# GMSL_DESERIALIZER.net
KiCad netlist of a schematic drawn in Altium Designer
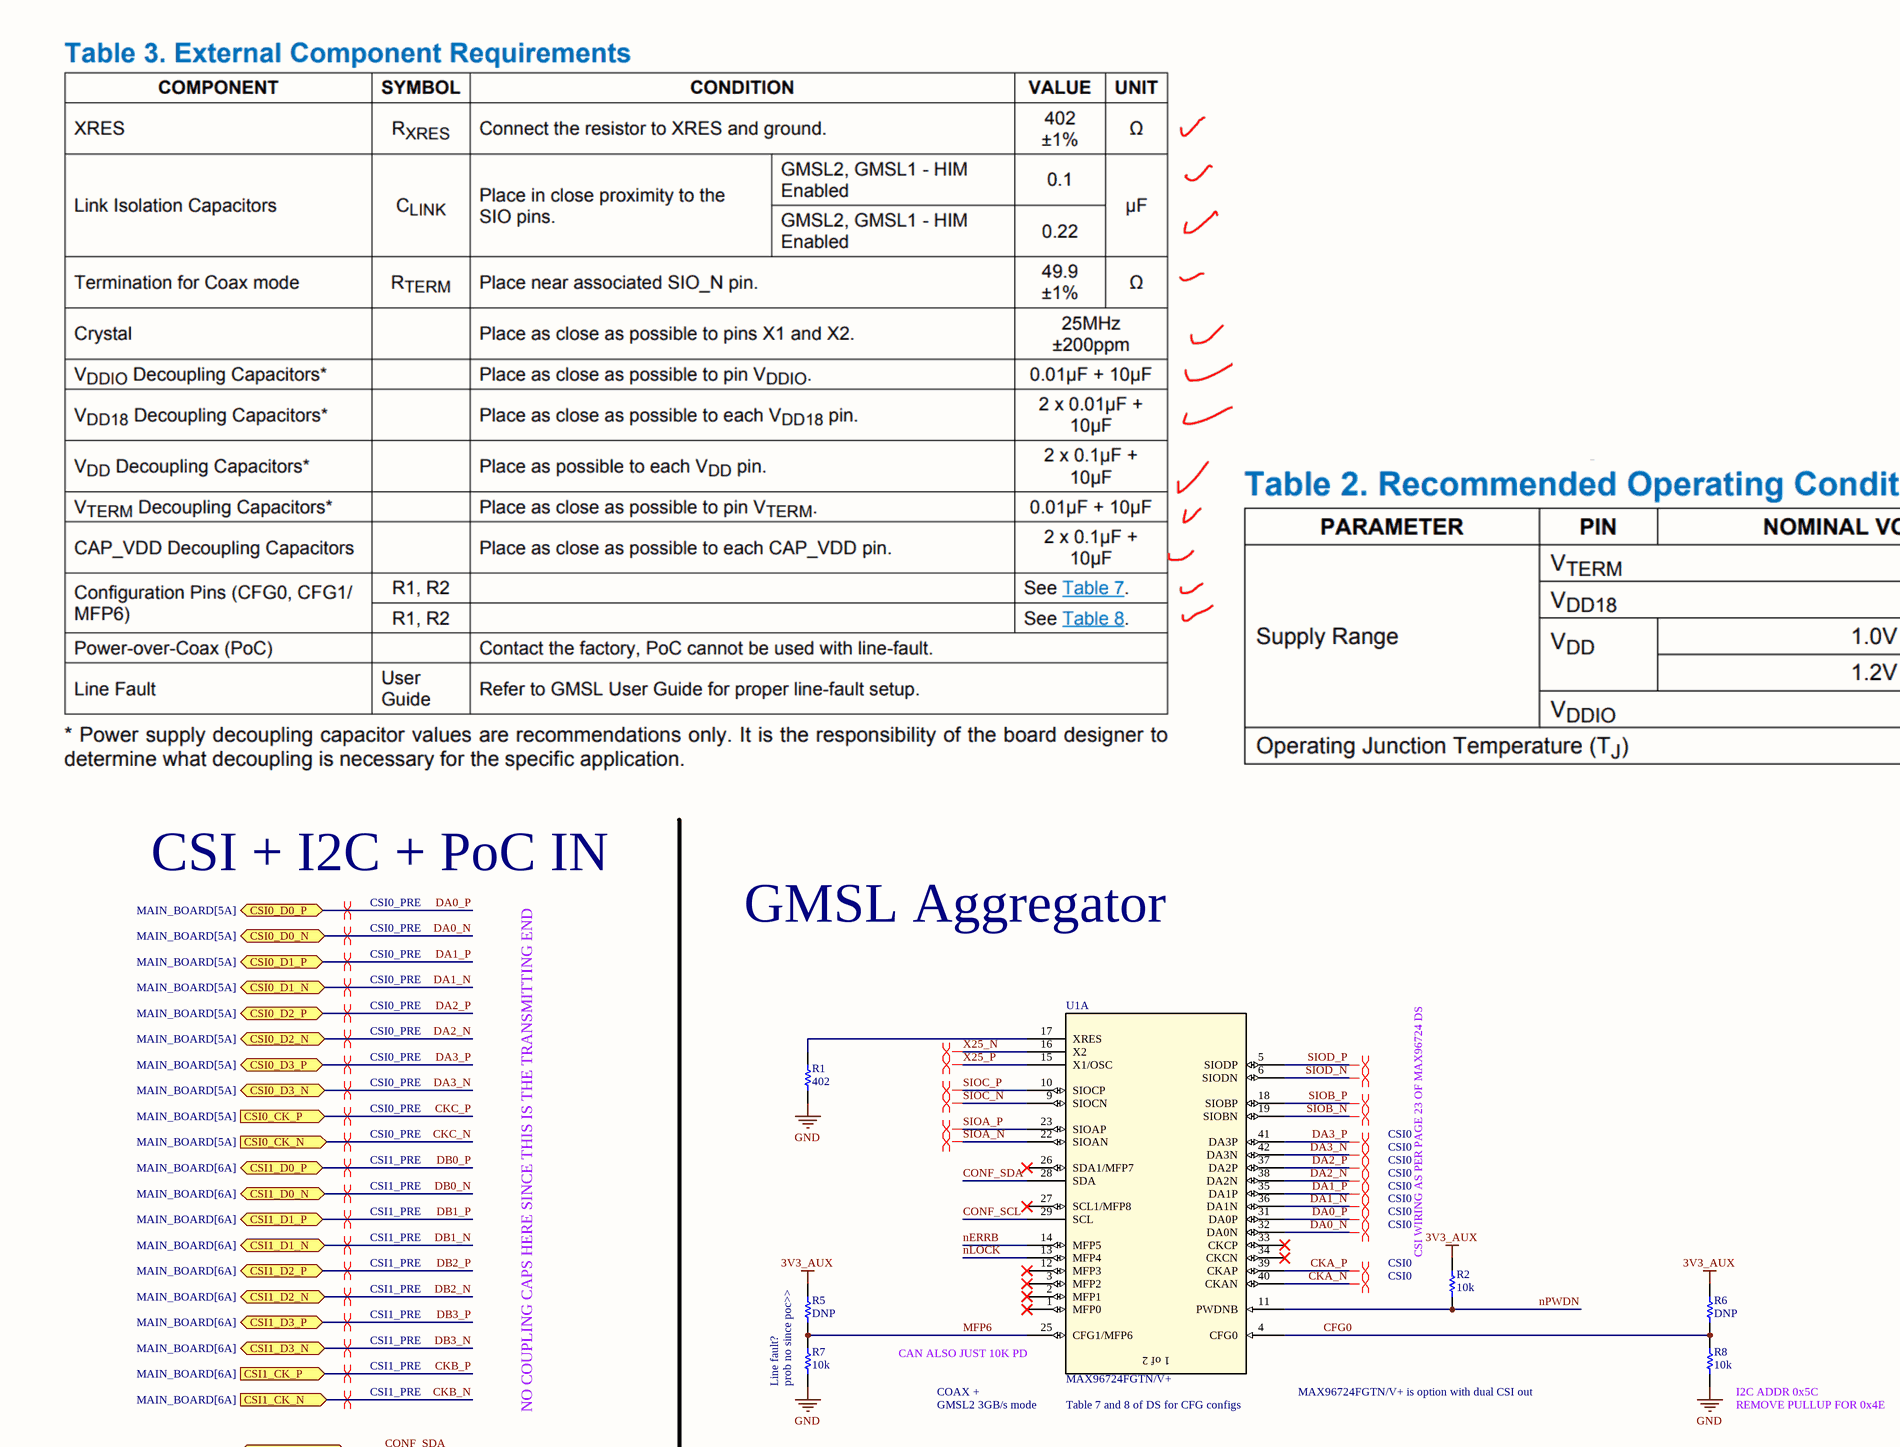
[diagram p0: GMSL_DESERIALIZER.SchDoc, top left]
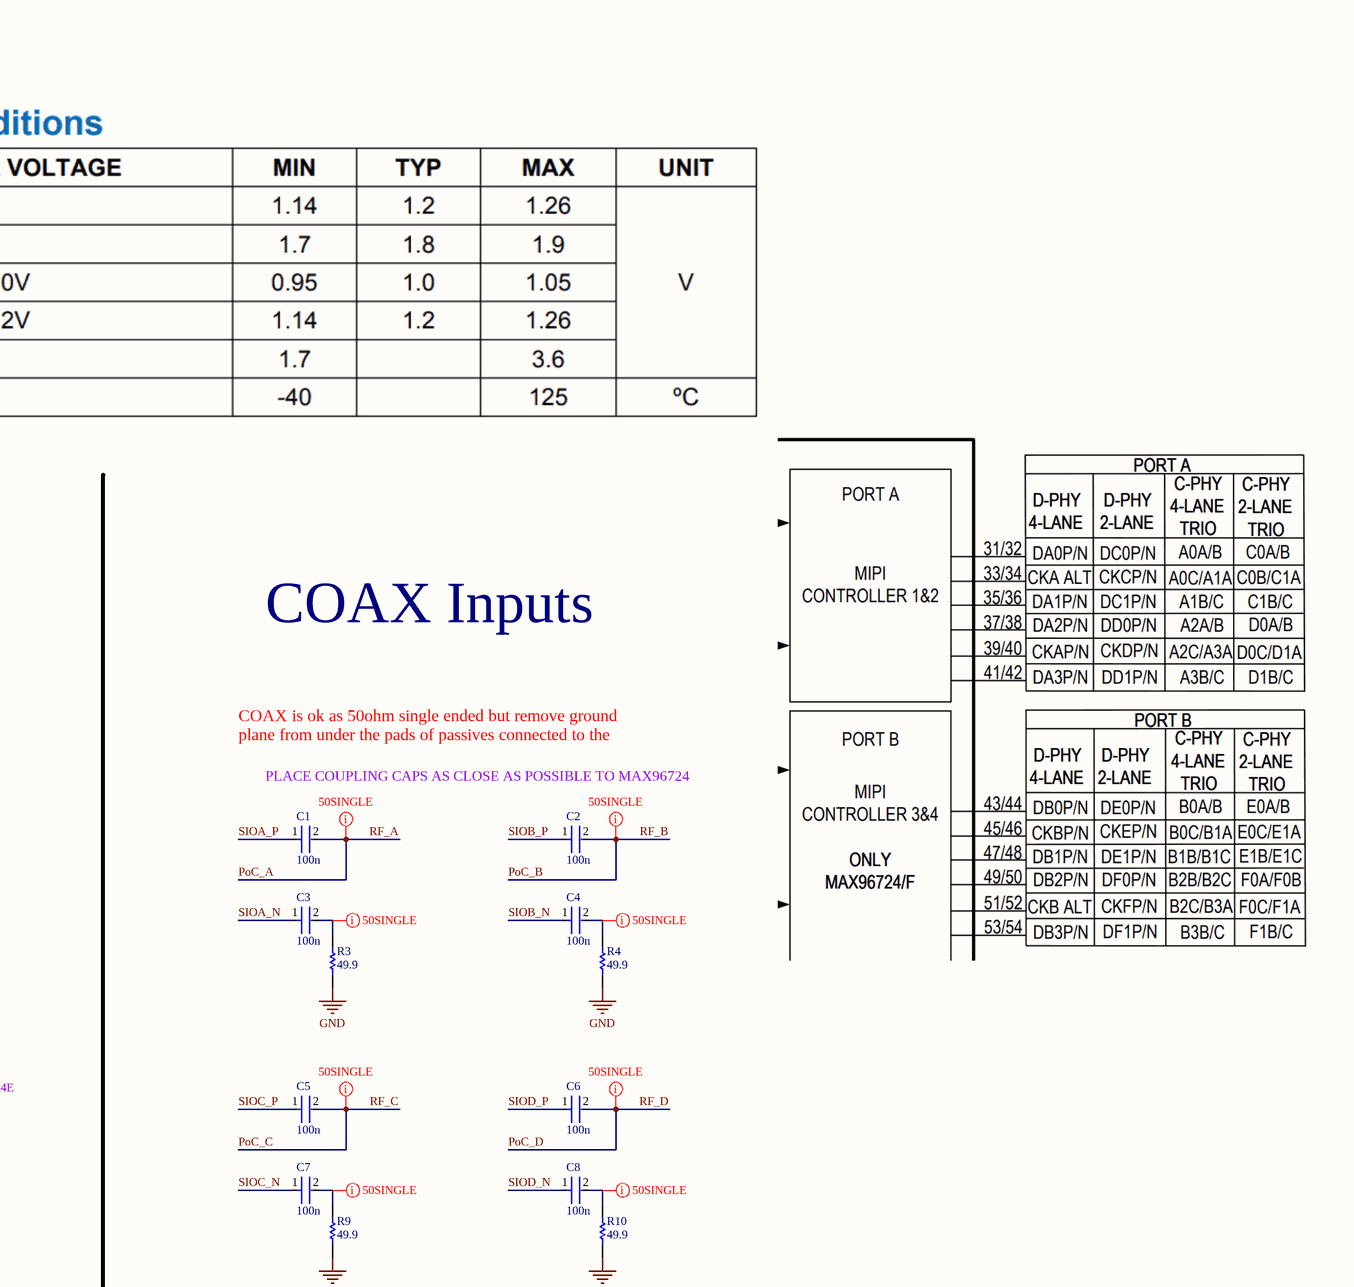
[diagram p1: GMSL_DESERIALIZER.SchDoc, top right]
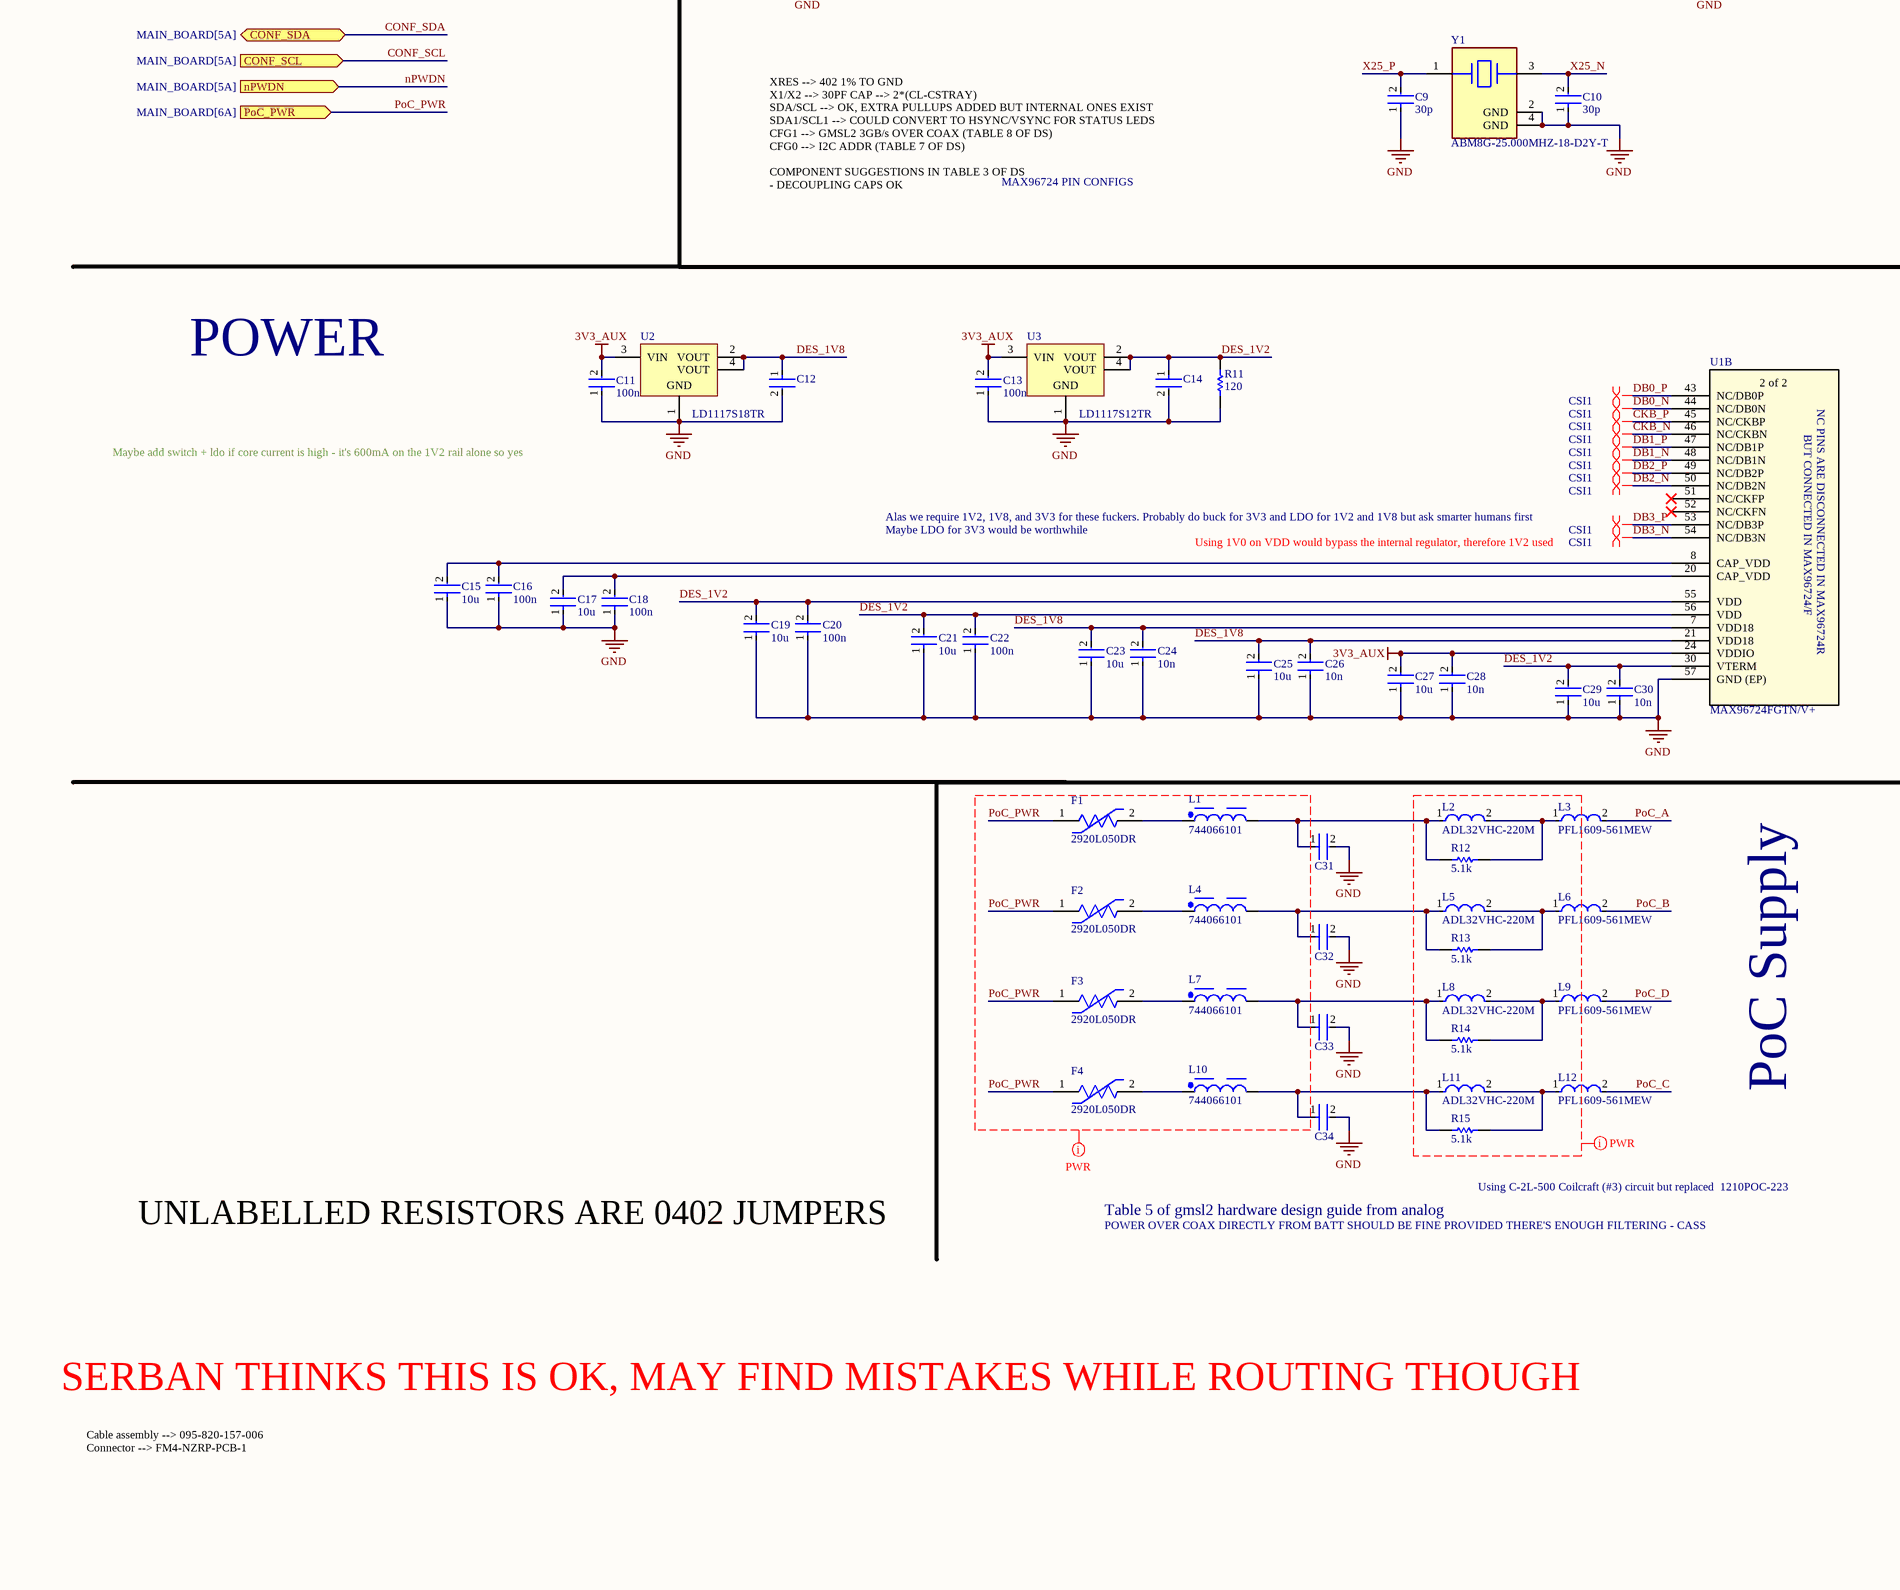
[diagram p2: GMSL_DESERIALIZER.SchDoc, bottom left]
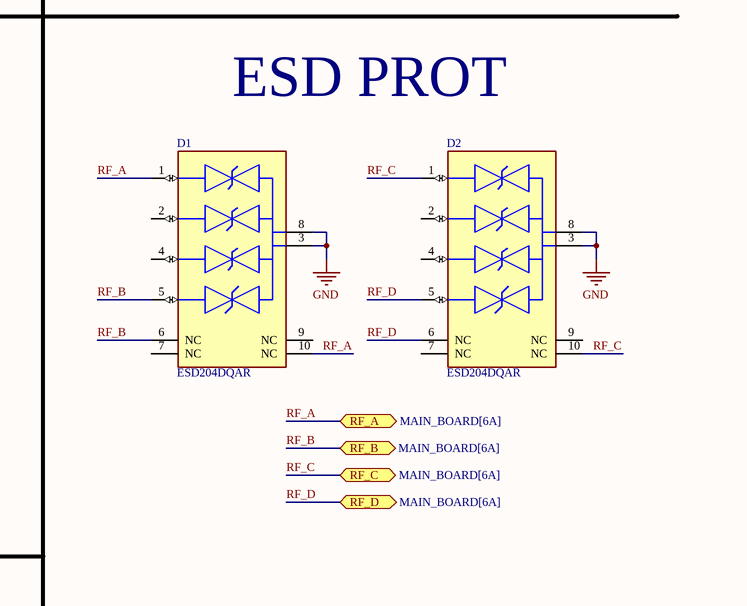
[diagram p3: GMSL_DESERIALIZER.SchDoc, bottom right]

(export (version "E")
  (design (tool "Eeschema 10.0.6"))
  (components
    (comp (ref "C1")
      (value "100n")
      (footprint "FP-0402-L_1_0_0_05-W_0_5-IPC_A")
      (description "LARGE PADS, 0402 CAP, CHANGE COMMENT TO MATCH REAL P/N")
      (libsource (lib "Space Concordia") (part "b4654b650e69147ec39a6b967a45e02"))
    )
    (comp (ref "C2")
      (value "100n")
      (footprint "FP-0402-L_1_0_0_05-W_0_5-IPC_A")
      (description "LARGE PADS, 0402 CAP, CHANGE COMMENT TO MATCH REAL P/N")
      (libsource (lib "Space Concordia") (part "b4654b650e69147ec39a6b967a45e02"))
    )
    (comp (ref "C3")
      (value "100n")
      (footprint "FP-0402-L_1_0_0_05-W_0_5-IPC_A")
      (description "LARGE PADS, 0402 CAP, CHANGE COMMENT TO MATCH REAL P/N")
      (libsource (lib "Space Concordia") (part "b4654b650e69147ec39a6b967a45e02"))
    )
    (comp (ref "C4")
      (value "100n")
      (footprint "FP-0402-L_1_0_0_05-W_0_5-IPC_A")
      (description "LARGE PADS, 0402 CAP, CHANGE COMMENT TO MATCH REAL P/N")
      (libsource (lib "Space Concordia") (part "b4654b650e69147ec39a6b967a45e02"))
    )
    (comp (ref "C5")
      (value "100n")
      (footprint "FP-0402-L_1_0_0_05-W_0_5-IPC_A")
      (description "LARGE PADS, 0402 CAP, CHANGE COMMENT TO MATCH REAL P/N")
      (libsource (lib "Space Concordia") (part "b4654b650e69147ec39a6b967a45e02"))
    )
    (comp (ref "C6")
      (value "100n")
      (footprint "FP-0402-L_1_0_0_05-W_0_5-IPC_A")
      (description "LARGE PADS, 0402 CAP, CHANGE COMMENT TO MATCH REAL P/N")
      (libsource (lib "Space Concordia") (part "b4654b650e69147ec39a6b967a45e02"))
    )
    (comp (ref "C7")
      (value "100n")
      (footprint "FP-0402-L_1_0_0_05-W_0_5-IPC_A")
      (description "LARGE PADS, 0402 CAP, CHANGE COMMENT TO MATCH REAL P/N")
      (libsource (lib "Space Concordia") (part "b4654b650e69147ec39a6b967a45e02"))
    )
    (comp (ref "C8")
      (value "100n")
      (footprint "FP-0402-L_1_0_0_05-W_0_5-IPC_A")
      (description "LARGE PADS, 0402 CAP, CHANGE COMMENT TO MATCH REAL P/N")
      (libsource (lib "Space Concordia") (part "b4654b650e69147ec39a6b967a45e02"))
    )
    (comp (ref "C9")
      (value "30p")
      (footprint "FP-0402-L_1_0_0_05-W_0_5-IPC_A")
      (description "LARGE PADS, 0402 CAP, CHANGE COMMENT TO MATCH REAL P/N")
      (libsource (lib "Space Concordia") (part "b4654b650e69147ec39a6b967a45e02"))
    )
    (comp (ref "C10")
      (value "30p")
      (footprint "FP-0402-L_1_0_0_05-W_0_5-IPC_A")
      (description "LARGE PADS, 0402 CAP, CHANGE COMMENT TO MATCH REAL P/N")
      (libsource (lib "Space Concordia") (part "b4654b650e69147ec39a6b967a45e02"))
    )
    (comp (ref "C11")
      (value "100n")
      (footprint "FP-0402-L_1_0_0_05-W_0_5-IPC_A")
      (description "LARGE PADS, 0402 CAP, CHANGE COMMENT TO MATCH REAL P/N")
      (libsource (lib "Space Concordia") (part "b4654b650e69147ec39a6b967a45e02"))
    )
    (comp (ref "C12")
      (value "GRM188R60J106ME47D")
      (footprint "FP-GRM188-0_1-e0_2_0_55-IPC_A")
      (description "Chip Multilayer Ceramic Capacitors for General Purpose, 0603, 10uF, X5R, 15%, 20%, 6.3V")
      (fields (field (name "VOLTAGE") "6.3V") (field (name "TOLERANCE") "20%"))
      (libsource (lib "Altium Content Vault") (part "02cd4be3c70576c341d710602a673aa"))
    )
    (comp (ref "C13")
      (value "100n")
      (footprint "FP-0402-L_1_0_0_05-W_0_5-IPC_A")
      (description "LARGE PADS, 0402 CAP, CHANGE COMMENT TO MATCH REAL P/N")
      (libsource (lib "Space Concordia") (part "b4654b650e69147ec39a6b967a45e02"))
    )
    (comp (ref "C14")
      (value "GRM188R60J106ME47D")
      (footprint "FP-GRM188-0_1-e0_2_0_55-IPC_A")
      (description "Chip Multilayer Ceramic Capacitors for General Purpose, 0603, 10uF, X5R, 15%, 20%, 6.3V")
      (fields (field (name "VOLTAGE") "6.3V") (field (name "TOLERANCE") "20%"))
      (libsource (lib "Altium Content Vault") (part "02cd4be3c70576c341d710602a673aa"))
    )
    (comp (ref "C15")
      (value "10u")
      (footprint "FP-0402-L_1_0_0_05-W_0_5-IPC_A")
      (description "LARGE PADS, 0402 CAP, CHANGE COMMENT TO MATCH REAL P/N")
      (libsource (lib "Space Concordia") (part "b4654b650e69147ec39a6b967a45e02"))
    )
    (comp (ref "C16")
      (value "100n")
      (footprint "FP-0402-L_1_0_0_05-W_0_5-IPC_A")
      (description "LARGE PADS, 0402 CAP, CHANGE COMMENT TO MATCH REAL P/N")
      (libsource (lib "Space Concordia") (part "b4654b650e69147ec39a6b967a45e02"))
    )
    (comp (ref "C17")
      (value "10u")
      (footprint "FP-0402-L_1_0_0_05-W_0_5-IPC_A")
      (description "LARGE PADS, 0402 CAP, CHANGE COMMENT TO MATCH REAL P/N")
      (libsource (lib "Space Concordia") (part "b4654b650e69147ec39a6b967a45e02"))
    )
    (comp (ref "C18")
      (value "100n")
      (footprint "FP-0402-L_1_0_0_05-W_0_5-IPC_A")
      (description "LARGE PADS, 0402 CAP, CHANGE COMMENT TO MATCH REAL P/N")
      (libsource (lib "Space Concordia") (part "b4654b650e69147ec39a6b967a45e02"))
    )
    (comp (ref "C19")
      (value "10u")
      (footprint "FP-0402-L_1_0_0_05-W_0_5-IPC_A")
      (description "LARGE PADS, 0402 CAP, CHANGE COMMENT TO MATCH REAL P/N")
      (libsource (lib "Space Concordia") (part "b4654b650e69147ec39a6b967a45e02"))
    )
    (comp (ref "C20")
      (value "100n")
      (footprint "FP-0402-L_1_0_0_05-W_0_5-IPC_A")
      (description "LARGE PADS, 0402 CAP, CHANGE COMMENT TO MATCH REAL P/N")
      (libsource (lib "Space Concordia") (part "b4654b650e69147ec39a6b967a45e02"))
    )
    (comp (ref "C21")
      (value "10u")
      (footprint "FP-0402-L_1_0_0_05-W_0_5-IPC_A")
      (description "LARGE PADS, 0402 CAP, CHANGE COMMENT TO MATCH REAL P/N")
      (libsource (lib "Space Concordia") (part "b4654b650e69147ec39a6b967a45e02"))
    )
    (comp (ref "C22")
      (value "100n")
      (footprint "FP-0402-L_1_0_0_05-W_0_5-IPC_A")
      (description "LARGE PADS, 0402 CAP, CHANGE COMMENT TO MATCH REAL P/N")
      (libsource (lib "Space Concordia") (part "b4654b650e69147ec39a6b967a45e02"))
    )
    (comp (ref "C23")
      (value "10u")
      (footprint "FP-0402-L_1_0_0_05-W_0_5-IPC_A")
      (description "LARGE PADS, 0402 CAP, CHANGE COMMENT TO MATCH REAL P/N")
      (libsource (lib "Space Concordia") (part "b4654b650e69147ec39a6b967a45e02"))
    )
    (comp (ref "C24")
      (value "10n")
      (footprint "FP-0402-L_1_0_0_05-W_0_5-IPC_A")
      (description "LARGE PADS, 0402 CAP, CHANGE COMMENT TO MATCH REAL P/N")
      (libsource (lib "Space Concordia") (part "b4654b650e69147ec39a6b967a45e02"))
    )
    (comp (ref "C25")
      (value "10u")
      (footprint "FP-0402-L_1_0_0_05-W_0_5-IPC_A")
      (description "LARGE PADS, 0402 CAP, CHANGE COMMENT TO MATCH REAL P/N")
      (libsource (lib "Space Concordia") (part "b4654b650e69147ec39a6b967a45e02"))
    )
    (comp (ref "C26")
      (value "10n")
      (footprint "FP-0402-L_1_0_0_05-W_0_5-IPC_A")
      (description "LARGE PADS, 0402 CAP, CHANGE COMMENT TO MATCH REAL P/N")
      (libsource (lib "Space Concordia") (part "b4654b650e69147ec39a6b967a45e02"))
    )
    (comp (ref "C27")
      (value "10u")
      (footprint "FP-0402-L_1_0_0_05-W_0_5-IPC_A")
      (description "LARGE PADS, 0402 CAP, CHANGE COMMENT TO MATCH REAL P/N")
      (libsource (lib "Space Concordia") (part "b4654b650e69147ec39a6b967a45e02"))
    )
    (comp (ref "C28")
      (value "10n")
      (footprint "FP-0402-L_1_0_0_05-W_0_5-IPC_A")
      (description "LARGE PADS, 0402 CAP, CHANGE COMMENT TO MATCH REAL P/N")
      (libsource (lib "Space Concordia") (part "b4654b650e69147ec39a6b967a45e02"))
    )
    (comp (ref "C29")
      (value "10u")
      (footprint "FP-0402-L_1_0_0_05-W_0_5-IPC_A")
      (description "LARGE PADS, 0402 CAP, CHANGE COMMENT TO MATCH REAL P/N")
      (libsource (lib "Space Concordia") (part "b4654b650e69147ec39a6b967a45e02"))
    )
    (comp (ref "C30")
      (value "10n")
      (footprint "FP-0402-L_1_0_0_05-W_0_5-IPC_A")
      (description "LARGE PADS, 0402 CAP, CHANGE COMMENT TO MATCH REAL P/N")
      (libsource (lib "Space Concordia") (part "b4654b650e69147ec39a6b967a45e02"))
    )
    (comp (ref "C31")
      (value "GRM21BR61E226ME44L")
      (footprint "FP-GRM21B-0_2-e0_2_0_7-IPC_B")
      (description "Chip Multilayer Ceramic Capacitors for General Purpose, 0805, 22uF, X5R, 15%, 20%, 25V")
      (fields (field (name "TOLERANCE") "20%") (field (name "VOLTAGE") "25V"))
      (libsource (lib "Altium Content Vault") (part "b4654b650e69147ec39a6b967a45e02"))
    )
    (comp (ref "C32")
      (value "GRM21BR61E226ME44L")
      (footprint "FP-GRM21B-0_2-e0_2_0_7-IPC_B")
      (description "Chip Multilayer Ceramic Capacitors for General Purpose, 0805, 22uF, X5R, 15%, 20%, 25V")
      (fields (field (name "TOLERANCE") "20%") (field (name "VOLTAGE") "25V"))
      (libsource (lib "Altium Content Vault") (part "b4654b650e69147ec39a6b967a45e02"))
    )
    (comp (ref "C33")
      (value "GRM21BR61E226ME44L")
      (footprint "FP-GRM21B-0_2-e0_2_0_7-IPC_B")
      (description "Chip Multilayer Ceramic Capacitors for General Purpose, 0805, 22uF, X5R, 15%, 20%, 25V")
      (fields (field (name "TOLERANCE") "20%") (field (name "VOLTAGE") "25V"))
      (libsource (lib "Altium Content Vault") (part "b4654b650e69147ec39a6b967a45e02"))
    )
    (comp (ref "C34")
      (value "GRM21BR61E226ME44L")
      (footprint "FP-GRM21B-0_2-e0_2_0_7-IPC_B")
      (description "Chip Multilayer Ceramic Capacitors for General Purpose, 0805, 22uF, X5R, 15%, 20%, 25V")
      (fields (field (name "TOLERANCE") "20%") (field (name "VOLTAGE") "25V"))
      (libsource (lib "Altium Content Vault") (part "b4654b650e69147ec39a6b967a45e02"))
    )
    (comp (ref "D1")
      (value "ESD204DQAR")
      (footprint "FP-DQA0010A-MFG")
      (description "4-CHANNEL LOW-CAPACITANCE SURGE")
      (fields
        (field (name "MANUFACTURER") "Texas Instruments")
        (field (name "OCTOPART") "https://octopart.com/esd204dqar-texas+instruments-89917476")
      )
      (libsource (lib "Altium Content Vault") (part "1465e58c1818c7767b55926832f0bf5"))
    )
    (comp (ref "D2")
      (value "ESD204DQAR")
      (footprint "FP-DQA0010A-MFG")
      (description "4-CHANNEL LOW-CAPACITANCE SURGE")
      (fields
        (field (name "MANUFACTURER") "Texas Instruments")
        (field (name "OCTOPART") "https://octopart.com/esd204dqar-texas+instruments-89917476")
      )
      (libsource (lib "Altium Content Vault") (part "1465e58c1818c7767b55926832f0bf5"))
    )
    (comp (ref "F1")
      (value "2920L050DR")
      (footprint "FP-2920L050DR-MFG")
      (description "PTC RESET FUSE 60V 500MA 2920")
      (libsource (lib "Altium Content Vault") (part "1c6d77a0208143737455a0c7eb396be"))
    )
    (comp (ref "F2")
      (value "2920L050DR")
      (footprint "FP-2920L050DR-MFG")
      (description "PTC RESET FUSE 60V 500MA 2920")
      (libsource (lib "Altium Content Vault") (part "1c6d77a0208143737455a0c7eb396be"))
    )
    (comp (ref "F3")
      (value "2920L050DR")
      (footprint "FP-2920L050DR-MFG")
      (description "PTC RESET FUSE 60V 500MA 2920")
      (libsource (lib "Altium Content Vault") (part "1c6d77a0208143737455a0c7eb396be"))
    )
    (comp (ref "F4")
      (value "2920L050DR")
      (footprint "FP-2920L050DR-MFG")
      (description "PTC RESET FUSE 60V 500MA 2920")
      (libsource (lib "Altium Content Vault") (part "1c6d77a0208143737455a0c7eb396be"))
    )
    (comp (ref "L1")
      (value "744066101")
      (footprint "WE-TPC_1038")
      (fields (field (name "TOLERANCE") "30%"))
      (libsource (lib "Altium Content Vault") (part "Inductor - 2"))
    )
    (comp (ref "L2")
      (value "ADL32VHC-220M")
      (footprint "FP-1210POC-MFG")
      (description "NOT COILCRAFT - ACTUAL P# --> ADL32VHC-220M\r\n - Power Injection Chokes for PoC")
      (fields
        (field (name "MANUFACTURER") "coilcraft")
        (field (name "OCTOPART") "https://octopart.com/1210poc-223mrc-coilcraft-103207315")
      )
      (libsource (lib "Altium Content Vault") (part "725321dda6339637d4d059423bc1c3c"))
    )
    (comp (ref "L3")
      (value "PFL1609-561MEW")
      (footprint "FP-PFL1609-MFG")
      (description "Fixed Inductors PFL1609 Low Profile 0.56 uH 20 % 1.4 A")
      (fields (field (name "MANUFACTURER") "coilcraft") (field (name "TOLERANCE") "20%"))
      (libsource (lib "Altium Content Vault") (part "725321dda6339637d4d059423bc1c3c"))
    )
    (comp (ref "L4")
      (value "744066101")
      (footprint "WE-TPC_1038")
      (fields (field (name "TOLERANCE") "30%"))
      (libsource (lib "Altium Content Vault") (part "Inductor - 2"))
    )
    (comp (ref "L5")
      (value "ADL32VHC-220M")
      (footprint "FP-1210POC-MFG")
      (description "NOT COILCRAFT - ACTUAL P# --> ADL32VHC-220M\r\n - Power Injection Chokes for PoC")
      (fields
        (field (name "MANUFACTURER") "coilcraft")
        (field (name "OCTOPART") "https://octopart.com/1210poc-223mrc-coilcraft-103207315")
      )
      (libsource (lib "Altium Content Vault") (part "725321dda6339637d4d059423bc1c3c"))
    )
    (comp (ref "L6")
      (value "PFL1609-561MEW")
      (footprint "FP-PFL1609-MFG")
      (description "Fixed Inductors PFL1609 Low Profile 0.56 uH 20 % 1.4 A")
      (fields (field (name "MANUFACTURER") "coilcraft") (field (name "TOLERANCE") "20%"))
      (libsource (lib "Altium Content Vault") (part "725321dda6339637d4d059423bc1c3c"))
    )
    (comp (ref "L7")
      (value "744066101")
      (footprint "WE-TPC_1038")
      (fields (field (name "TOLERANCE") "30%"))
      (libsource (lib "Altium Content Vault") (part "Inductor - 2"))
    )
    (comp (ref "L8")
      (value "ADL32VHC-220M")
      (footprint "FP-1210POC-MFG")
      (description "NOT COILCRAFT - ACTUAL P# --> ADL32VHC-220M\r\n - Power Injection Chokes for PoC")
      (fields
        (field (name "MANUFACTURER") "coilcraft")
        (field (name "OCTOPART") "https://octopart.com/1210poc-223mrc-coilcraft-103207315")
      )
      (libsource (lib "Altium Content Vault") (part "725321dda6339637d4d059423bc1c3c"))
    )
    (comp (ref "L9")
      (value "PFL1609-561MEW")
      (footprint "FP-PFL1609-MFG")
      (description "Fixed Inductors PFL1609 Low Profile 0.56 uH 20 % 1.4 A")
      (fields (field (name "MANUFACTURER") "coilcraft") (field (name "TOLERANCE") "20%"))
      (libsource (lib "Altium Content Vault") (part "725321dda6339637d4d059423bc1c3c"))
    )
    (comp (ref "L10")
      (value "744066101")
      (footprint "WE-TPC_1038")
      (fields (field (name "TOLERANCE") "30%"))
      (libsource (lib "Altium Content Vault") (part "Inductor - 2"))
    )
    (comp (ref "L11")
      (value "ADL32VHC-220M")
      (footprint "FP-1210POC-MFG")
      (description "NOT COILCRAFT - ACTUAL P# --> ADL32VHC-220M\r\n - Power Injection Chokes for PoC")
      (fields
        (field (name "MANUFACTURER") "coilcraft")
        (field (name "OCTOPART") "https://octopart.com/1210poc-223mrc-coilcraft-103207315")
      )
      (libsource (lib "Altium Content Vault") (part "725321dda6339637d4d059423bc1c3c"))
    )
    (comp (ref "L12")
      (value "PFL1609-561MEW")
      (footprint "FP-PFL1609-MFG")
      (description "Fixed Inductors PFL1609 Low Profile 0.56 uH 20 % 1.4 A")
      (fields (field (name "MANUFACTURER") "coilcraft") (field (name "TOLERANCE") "20%"))
      (libsource (lib "Altium Content Vault") (part "725321dda6339637d4d059423bc1c3c"))
    )
    (comp (ref "R1")
      (value "402")
      (footprint "R0603B")
      (description "Resistor")
      (libsource (lib "Space Concordia") (part "Resistor"))
    )
    (comp (ref "R2")
      (value "10k")
      (footprint "R0603B")
      (description "Resistor")
      (libsource (lib "Space Concordia") (part "Resistor"))
    )
    (comp (ref "R3")
      (value "49.9")
      (footprint "R0603B")
      (description "Resistor")
      (libsource (lib "Space Concordia") (part "Resistor"))
    )
    (comp (ref "R4")
      (value "49.9")
      (footprint "R0603B")
      (description "Resistor")
      (libsource (lib "Space Concordia") (part "Resistor"))
    )
    (comp (ref "R5")
      (value "DNP")
      (footprint "R0603B")
      (description "Resistor")
      (libsource (lib "Space Concordia") (part "Resistor"))
    )
    (comp (ref "R6")
      (value "DNP")
      (footprint "R0603B")
      (description "Resistor")
      (libsource (lib "Space Concordia") (part "Resistor"))
    )
    (comp (ref "R7")
      (value "10k")
      (footprint "R0603B")
      (description "Resistor")
      (libsource (lib "Space Concordia") (part "Resistor"))
    )
    (comp (ref "R8")
      (value "10k")
      (footprint "R0603B")
      (description "Resistor")
      (libsource (lib "Space Concordia") (part "Resistor"))
    )
    (comp (ref "R9")
      (value "49.9")
      (footprint "R0603B")
      (description "Resistor")
      (libsource (lib "Space Concordia") (part "Resistor"))
    )
    (comp (ref "R10")
      (value "49.9")
      (footprint "R0603B")
      (description "Resistor")
      (libsource (lib "Space Concordia") (part "Resistor"))
    )
    (comp (ref "R11")
      (value "120")
      (footprint "R0603B")
      (description "Resistor")
      (libsource (lib "Space Concordia") (part "Resistor"))
    )
    (comp (ref "R12")
      (value "5.1k")
      (footprint "R0603B")
      (description "Resistor")
      (libsource (lib "Space Concordia") (part "Resistor"))
    )
    (comp (ref "R13")
      (value "5.1k")
      (footprint "R0603B")
      (description "Resistor")
      (libsource (lib "Space Concordia") (part "Resistor"))
    )
    (comp (ref "R14")
      (value "5.1k")
      (footprint "R0603B")
      (description "Resistor")
      (libsource (lib "Space Concordia") (part "Resistor"))
    )
    (comp (ref "R15")
      (value "5.1k")
      (footprint "R0603B")
      (description "Resistor")
      (libsource (lib "Space Concordia") (part "Resistor"))
    )
    (comp (ref "U1")
      (value "MAX96724FGTN/V+")
      (footprint "MAX96724FGTN_V+-Footprint-1")
      (description "Quad Tunneling GMSL2/1 to CSI-2 Deserializer")
      (libsource (lib "Space Concordia") (part "MAX96724FGTN_V+-Symbol-1"))
    )
    (comp (ref "U2")
      (value "LD1117S18TR")
      (footprint "SOT-223_M")
      (description "Fixed Low Drop Positive Voltage Regulator, 1.8V, 4-Pin SOT-223, Tape and Reel")
      (libsource (lib "Altium Content Vault") (part "PM-REG-LD1117-SOT4"))
    )
    (comp (ref "U3")
      (value "LD1117S12TR")
      (footprint "SOT-223_M")
      (description "Fixed Low Drop Positive Voltage Regulator, 1.2V, 4-Pin SOT-223, Tape and Reel")
      (libsource (lib "Altium Content Vault") (part "PM-REG-LD1117-SOT4"))
    )
    (comp (ref "Y1")
      (value "ABM8G-25.000MHZ-18-D2Y-T")
      (footprint "FP-ABM8G-MFG")
      (description "Crystal 25MHz ±20ppm (Tol) ±30ppm (Stability) 18pF FUND 60Ω 4-Pin SMD T/R")
      (fields (field (name "TOLERANCE") "20ppm"))
      (libsource (lib "Altium Content Vault") (part "48e526d86b7f2615d98721063c72f49"))
    )
  )
  (nets
    (net (code "1") (name "/CFG0") (class "Default")
      (node (ref "R6") (pin "1") (pinfunction "1_1") (pintype "passive"))
      (node (ref "R8") (pin "2") (pinfunction "2_2") (pintype "passive"))
      (node (ref "U1") (pin "4") (pinfunction "CFG0_4") (pintype "input"))
    )
    (net (code "2") (name "/CKA_N") (class "Default")
      (node (ref "U1") (pin "40") (pinfunction "CKAN_40") (pintype "bidirectional"))
    )
    (net (code "3") (name "/CKA_P") (class "Default")
      (node (ref "U1") (pin "39") (pinfunction "CKAP_39") (pintype "bidirectional"))
    )
    (net (code "4") (name "/CKB_N") (class "Default")
      (node (ref "U1") (pin "46") (pinfunction "NC/CKBN_46") (pintype "passive"))
    )
    (net (code "5") (name "/CKB_P") (class "Default")
      (node (ref "U1") (pin "45") (pinfunction "NC/CKBP_45") (pintype "passive"))
    )
    (net (code "8") (name "/CONF_SCL") (class "Default")
      (node (ref "U1") (pin "29") (pinfunction "SCL_29") (pintype "passive"))
    )
    (net (code "9") (name "/CONF_SDA") (class "Default")
      (node (ref "U1") (pin "28") (pinfunction "SDA_28") (pintype "passive"))
    )
    (net (code "10") (name "/DA0_N") (class "Default")
      (node (ref "U1") (pin "32") (pinfunction "DA0N_32") (pintype "bidirectional"))
    )
    (net (code "11") (name "/DA0_P") (class "Default")
      (node (ref "U1") (pin "31") (pinfunction "DA0P_31") (pintype "bidirectional"))
    )
    (net (code "12") (name "/DA1_N") (class "Default")
      (node (ref "U1") (pin "36") (pinfunction "DA1N_36") (pintype "bidirectional"))
    )
    (net (code "13") (name "/DA1_P") (class "Default")
      (node (ref "U1") (pin "35") (pinfunction "DA1P_35") (pintype "bidirectional"))
    )
    (net (code "14") (name "/DA2_N") (class "Default")
      (node (ref "U1") (pin "38") (pinfunction "DA2N_38") (pintype "bidirectional"))
    )
    (net (code "15") (name "/DA2_P") (class "Default")
      (node (ref "U1") (pin "37") (pinfunction "DA2P_37") (pintype "bidirectional"))
    )
    (net (code "16") (name "/DA3_N") (class "Default")
      (node (ref "U1") (pin "42") (pinfunction "DA3N_42") (pintype "bidirectional"))
    )
    (net (code "17") (name "/DA3_P") (class "Default")
      (node (ref "U1") (pin "41") (pinfunction "DA3P_41") (pintype "bidirectional"))
    )
    (net (code "18") (name "/DB0_N") (class "Default")
      (node (ref "U1") (pin "44") (pinfunction "NC/DB0N_44") (pintype "passive"))
    )
    (net (code "19") (name "/DB0_P") (class "Default")
      (node (ref "U1") (pin "43") (pinfunction "NC/DB0P_43") (pintype "passive"))
    )
    (net (code "20") (name "/DB1_N") (class "Default")
      (node (ref "U1") (pin "48") (pinfunction "NC/DB1N_48") (pintype "passive"))
    )
    (net (code "21") (name "/DB1_P") (class "Default")
      (node (ref "U1") (pin "47") (pinfunction "NC/DB1P_47") (pintype "passive"))
    )
    (net (code "22") (name "/DB2_N") (class "Default")
      (node (ref "U1") (pin "50") (pinfunction "NC/DB2N_50") (pintype "passive"))
    )
    (net (code "23") (name "/DB2_P") (class "Default")
      (node (ref "U1") (pin "49") (pinfunction "NC/DB2P_49") (pintype "passive"))
    )
    (net (code "24") (name "/DB3_N") (class "Default")
      (node (ref "U1") (pin "54") (pinfunction "NC/DB3N_54") (pintype "passive"))
    )
    (net (code "25") (name "/DB3_P") (class "Default")
      (node (ref "U1") (pin "53") (pinfunction "NC/DB3P_53") (pintype "passive"))
    )
    (net (code "26") (name "/DES_1V2") (class "Default")
      (node (ref "C14") (pin "1") (pinfunction "1_1") (pintype "passive"))
      (node (ref "C19") (pin "2") (pinfunction "2_2") (pintype "passive"))
      (node (ref "C20") (pin "2") (pinfunction "2_2") (pintype "passive"))
      (node (ref "C21") (pin "2") (pinfunction "2_2") (pintype "passive"))
      (node (ref "C22") (pin "2") (pinfunction "2_2") (pintype "passive"))
      (node (ref "C29") (pin "2") (pinfunction "2_2") (pintype "passive"))
      (node (ref "C30") (pin "2") (pinfunction "2_2") (pintype "passive"))
      (node (ref "R11") (pin "2") (pinfunction "2_2") (pintype "passive"))
      (node (ref "U1") (pin "30") (pinfunction "VTERM_30") (pintype "power_in"))
      (node (ref "U1") (pin "55") (pinfunction "VDD_55") (pintype "power_in"))
      (node (ref "U1") (pin "56") (pinfunction "VDD_56") (pintype "power_in"))
      (node (ref "U3") (pin "2") (pinfunction "VOUT_2") (pintype "power_in"))
      (node (ref "U3") (pin "4") (pinfunction "VOUT_4") (pintype "power_in"))
    )
    (net (code "27") (name "/DES_1V8") (class "Default")
      (node (ref "C12") (pin "1") (pinfunction "1_1") (pintype "passive"))
      (node (ref "C23") (pin "2") (pinfunction "2_2") (pintype "passive"))
      (node (ref "C24") (pin "2") (pinfunction "2_2") (pintype "passive"))
      (node (ref "C25") (pin "2") (pinfunction "2_2") (pintype "passive"))
      (node (ref "C26") (pin "2") (pinfunction "2_2") (pintype "passive"))
      (node (ref "U1") (pin "21") (pinfunction "VDD18_21") (pintype "power_in"))
      (node (ref "U1") (pin "7") (pinfunction "VDD18_7") (pintype "power_in"))
      (node (ref "U2") (pin "2") (pinfunction "VOUT_2") (pintype "power_in"))
      (node (ref "U2") (pin "4") (pinfunction "VOUT_4") (pintype "power_in"))
    )
    (net (code "28") (name "/MFP6") (class "Default")
      (node (ref "R5") (pin "1") (pinfunction "1_1") (pintype "passive"))
      (node (ref "R7") (pin "2") (pinfunction "2_2") (pintype "passive"))
      (node (ref "U1") (pin "25") (pinfunction "CFG1/MFP6_25") (pintype "bidirectional"))
    )
    (net (code "29") (name "/PoC_A") (class "Default")
      (node (ref "C1") (pin "2") (pinfunction "2_2") (pintype "passive"))
      (node (ref "D1") (pin "1") (pinfunction "IO1_1") (pintype "bidirectional"))
      (node (ref "D1") (pin "10") (pinfunction "NC_10") (pintype "passive"))
      (node (ref "L3") (pin "2") (pinfunction "2_2") (pintype "passive"))
    )
    (net (code "30") (name "/PoC_B") (class "Default")
      (node (ref "C2") (pin "2") (pinfunction "2_2") (pintype "passive"))
      (node (ref "D1") (pin "5") (pinfunction "IO4_5") (pintype "bidirectional"))
      (node (ref "D1") (pin "6") (pinfunction "NC_6") (pintype "passive"))
      (node (ref "L6") (pin "2") (pinfunction "2_2") (pintype "passive"))
    )
    (net (code "31") (name "/PoC_C") (class "Default")
      (node (ref "C5") (pin "2") (pinfunction "2_2") (pintype "passive"))
      (node (ref "D2") (pin "1") (pinfunction "IO1_1") (pintype "bidirectional"))
      (node (ref "D2") (pin "10") (pinfunction "NC_10") (pintype "passive"))
      (node (ref "L12") (pin "2") (pinfunction "2_2") (pintype "passive"))
    )
    (net (code "32") (name "/PoC_D") (class "Default")
      (node (ref "C6") (pin "2") (pinfunction "2_2") (pintype "passive"))
      (node (ref "D2") (pin "5") (pinfunction "IO4_5") (pintype "bidirectional"))
      (node (ref "D2") (pin "6") (pinfunction "NC_6") (pintype "passive"))
      (node (ref "L9") (pin "2") (pinfunction "2_2") (pintype "passive"))
    )
    (net (code "33") (name "/PoC_PWR") (class "Default")
      (node (ref "F1") (pin "1") (pinfunction "1_1") (pintype "passive"))
      (node (ref "F2") (pin "1") (pinfunction "1_1") (pintype "passive"))
      (node (ref "F3") (pin "1") (pinfunction "1_1") (pintype "passive"))
      (node (ref "F4") (pin "1") (pinfunction "1_1") (pintype "passive"))
    )
    (net (code "34") (name "/SIOA_N") (class "Default")
      (node (ref "C3") (pin "1") (pinfunction "1_1") (pintype "passive"))
      (node (ref "U1") (pin "22") (pinfunction "SIOAN_22") (pintype "bidirectional"))
    )
    (net (code "35") (name "/SIOA_P") (class "Default")
      (node (ref "C1") (pin "1") (pinfunction "1_1") (pintype "passive"))
      (node (ref "U1") (pin "23") (pinfunction "SIOAP_23") (pintype "bidirectional"))
    )
    (net (code "36") (name "/SIOB_N") (class "Default")
      (node (ref "C4") (pin "1") (pinfunction "1_1") (pintype "passive"))
      (node (ref "U1") (pin "19") (pinfunction "SIOBN_19") (pintype "bidirectional"))
    )
    (net (code "37") (name "/SIOB_P") (class "Default")
      (node (ref "C2") (pin "1") (pinfunction "1_1") (pintype "passive"))
      (node (ref "U1") (pin "18") (pinfunction "SIOBP_18") (pintype "bidirectional"))
    )
    (net (code "38") (name "/SIOC_N") (class "Default")
      (node (ref "C7") (pin "1") (pinfunction "1_1") (pintype "passive"))
      (node (ref "U1") (pin "9") (pinfunction "SIOCN_9") (pintype "bidirectional"))
    )
    (net (code "39") (name "/SIOC_P") (class "Default")
      (node (ref "C5") (pin "1") (pinfunction "1_1") (pintype "passive"))
      (node (ref "U1") (pin "10") (pinfunction "SIOCP_10") (pintype "bidirectional"))
    )
    (net (code "40") (name "/SIOD_N") (class "Default")
      (node (ref "C8") (pin "1") (pinfunction "1_1") (pintype "passive"))
      (node (ref "U1") (pin "6") (pinfunction "SIODN_6") (pintype "bidirectional"))
    )
    (net (code "41") (name "/SIOD_P") (class "Default")
      (node (ref "C6") (pin "1") (pinfunction "1_1") (pintype "passive"))
      (node (ref "U1") (pin "5") (pinfunction "SIODP_5") (pintype "bidirectional"))
    )
    (net (code "42") (name "/X25_N") (class "Default")
      (node (ref "C10") (pin "2") (pinfunction "2_2") (pintype "passive"))
      (node (ref "U1") (pin "16") (pinfunction "X2_16") (pintype "passive"))
      (node (ref "Y1") (pin "3") (pinfunction "3_3") (pintype "passive"))
    )
    (net (code "43") (name "/X25_P") (class "Default")
      (node (ref "C9") (pin "2") (pinfunction "2_2") (pintype "passive"))
      (node (ref "U1") (pin "15") (pinfunction "X1/OSC_15") (pintype "passive"))
      (node (ref "Y1") (pin "1") (pinfunction "1_1") (pintype "passive"))
    )
    (net (code "44") (name "/nERRB") (class "Default")
      (node (ref "U1") (pin "14") (pinfunction "MFP5_14") (pintype "bidirectional"))
    )
    (net (code "45") (name "/nLOCK") (class "Default")
      (node (ref "U1") (pin "13") (pinfunction "MFP4_13") (pintype "bidirectional"))
    )
    (net (code "46") (name "/nPWDN") (class "Default")
      (node (ref "R2") (pin "1") (pinfunction "1_1") (pintype "passive"))
      (node (ref "U1") (pin "11") (pinfunction "PWDNB_11") (pintype "input"))
    )
    (net (code "47") (name "3V3_AUX") (class "Default")
      (node (ref "C11") (pin "2") (pinfunction "2_2") (pintype "passive"))
      (node (ref "C13") (pin "2") (pinfunction "2_2") (pintype "passive"))
      (node (ref "C27") (pin "2") (pinfunction "2_2") (pintype "passive"))
      (node (ref "C28") (pin "2") (pinfunction "2_2") (pintype "passive"))
      (node (ref "R2") (pin "2") (pinfunction "2_2") (pintype "passive"))
      (node (ref "R5") (pin "2") (pinfunction "2_2") (pintype "passive"))
      (node (ref "R6") (pin "2") (pinfunction "2_2") (pintype "passive"))
      (node (ref "U1") (pin "24") (pinfunction "VDDIO_24") (pintype "power_in"))
      (node (ref "U2") (pin "3") (pinfunction "VIN_3") (pintype "power_in"))
      (node (ref "U3") (pin "3") (pinfunction "VIN_3") (pintype "power_in"))
    )
    (net (code "48") (name "GND") (class "Default")
      (node (ref "C10") (pin "1") (pinfunction "1_1") (pintype "passive"))
      (node (ref "C11") (pin "1") (pinfunction "1_1") (pintype "passive"))
      (node (ref "C12") (pin "2") (pinfunction "2_2") (pintype "passive"))
      (node (ref "C13") (pin "1") (pinfunction "1_1") (pintype "passive"))
      (node (ref "C14") (pin "2") (pinfunction "2_2") (pintype "passive"))
      (node (ref "C15") (pin "1") (pinfunction "1_1") (pintype "passive"))
      (node (ref "C16") (pin "1") (pinfunction "1_1") (pintype "passive"))
      (node (ref "C17") (pin "1") (pinfunction "1_1") (pintype "passive"))
      (node (ref "C18") (pin "1") (pinfunction "1_1") (pintype "passive"))
      (node (ref "C19") (pin "1") (pinfunction "1_1") (pintype "passive"))
      (node (ref "C20") (pin "1") (pinfunction "1_1") (pintype "passive"))
      (node (ref "C21") (pin "1") (pinfunction "1_1") (pintype "passive"))
      (node (ref "C22") (pin "1") (pinfunction "1_1") (pintype "passive"))
      (node (ref "C23") (pin "1") (pinfunction "1_1") (pintype "passive"))
      (node (ref "C24") (pin "1") (pinfunction "1_1") (pintype "passive"))
      (node (ref "C25") (pin "1") (pinfunction "1_1") (pintype "passive"))
      (node (ref "C26") (pin "1") (pinfunction "1_1") (pintype "passive"))
      (node (ref "C27") (pin "1") (pinfunction "1_1") (pintype "passive"))
      (node (ref "C28") (pin "1") (pinfunction "1_1") (pintype "passive"))
      (node (ref "C29") (pin "1") (pinfunction "1_1") (pintype "passive"))
      (node (ref "C30") (pin "1") (pinfunction "1_1") (pintype "passive"))
      (node (ref "C31") (pin "2") (pinfunction "2_2") (pintype "passive"))
      (node (ref "C32") (pin "2") (pinfunction "2_2") (pintype "passive"))
      (node (ref "C33") (pin "2") (pinfunction "2_2") (pintype "passive"))
      (node (ref "C34") (pin "2") (pinfunction "2_2") (pintype "passive"))
      (node (ref "C9") (pin "1") (pinfunction "1_1") (pintype "passive"))
      (node (ref "D1") (pin "3") (pinfunction "GND_3") (pintype "power_in"))
      (node (ref "D1") (pin "8") (pinfunction "GND_8") (pintype "power_in"))
      (node (ref "D2") (pin "3") (pinfunction "GND_3") (pintype "power_in"))
      (node (ref "D2") (pin "8") (pinfunction "GND_8") (pintype "power_in"))
      (node (ref "R1") (pin "1") (pinfunction "1_1") (pintype "passive"))
      (node (ref "R10") (pin "1") (pinfunction "1_1") (pintype "passive"))
      (node (ref "R11") (pin "1") (pinfunction "1_1") (pintype "passive"))
      (node (ref "R3") (pin "1") (pinfunction "1_1") (pintype "passive"))
      (node (ref "R4") (pin "1") (pinfunction "1_1") (pintype "passive"))
      (node (ref "R7") (pin "1") (pinfunction "1_1") (pintype "passive"))
      (node (ref "R8") (pin "1") (pinfunction "1_1") (pintype "passive"))
      (node (ref "R9") (pin "1") (pinfunction "1_1") (pintype "passive"))
      (node (ref "U1") (pin "57") (pinfunction "GND_(EP)_57") (pintype "power_in"))
      (node (ref "U2") (pin "1") (pinfunction "GND_1") (pintype "power_in"))
      (node (ref "U3") (pin "1") (pinfunction "GND_1") (pintype "power_in"))
      (node (ref "Y1") (pin "2") (pinfunction "GND_2") (pintype "power_in"))
      (node (ref "Y1") (pin "4") (pinfunction "GND_4") (pintype "power_in"))
    )
    (net (code "49") (name "Net-(C3-Pad2)") (class "Default")
      (node (ref "C3") (pin "2") (pinfunction "2_2") (pintype "passive"))
      (node (ref "R3") (pin "2") (pinfunction "2_2") (pintype "passive"))
    )
    (net (code "50") (name "Net-(C4-Pad2)") (class "Default")
      (node (ref "C4") (pin "2") (pinfunction "2_2") (pintype "passive"))
      (node (ref "R4") (pin "2") (pinfunction "2_2") (pintype "passive"))
    )
    (net (code "51") (name "Net-(C7-Pad2)") (class "Default")
      (node (ref "C7") (pin "2") (pinfunction "2_2") (pintype "passive"))
      (node (ref "R9") (pin "2") (pinfunction "2_2") (pintype "passive"))
    )
    (net (code "52") (name "Net-(C8-Pad2)") (class "Default")
      (node (ref "C8") (pin "2") (pinfunction "2_2") (pintype "passive"))
      (node (ref "R10") (pin "2") (pinfunction "2_2") (pintype "passive"))
    )
    (net (code "53") (name "Net-(C15-Pad2)") (class "Default")
      (node (ref "C15") (pin "2") (pinfunction "2_2") (pintype "passive"))
      (node (ref "C16") (pin "2") (pinfunction "2_2") (pintype "passive"))
      (node (ref "U1") (pin "8") (pinfunction "CAP_VDD_8") (pintype "power_in"))
    )
    (net (code "54") (name "Net-(C17-Pad2)") (class "Default")
      (node (ref "C17") (pin "2") (pinfunction "2_2") (pintype "passive"))
      (node (ref "C18") (pin "2") (pinfunction "2_2") (pintype "passive"))
      (node (ref "U1") (pin "20") (pinfunction "CAP_VDD_20") (pintype "power_in"))
    )
    (net (code "55") (name "Net-(C31-Pad1)") (class "Default")
      (node (ref "C31") (pin "1") (pinfunction "1_1") (pintype "passive"))
      (node (ref "L1") (pin "2") (pinfunction "2_2") (pintype "passive"))
      (node (ref "L2") (pin "1") (pinfunction "1_1") (pintype "passive"))
      (node (ref "R12") (pin "2") (pinfunction "2_2") (pintype "passive"))
    )
    (net (code "56") (name "Net-(C32-Pad1)") (class "Default")
      (node (ref "C32") (pin "1") (pinfunction "1_1") (pintype "passive"))
      (node (ref "L4") (pin "2") (pinfunction "2_2") (pintype "passive"))
      (node (ref "L5") (pin "1") (pinfunction "1_1") (pintype "passive"))
      (node (ref "R13") (pin "2") (pinfunction "2_2") (pintype "passive"))
    )
    (net (code "57") (name "Net-(C33-Pad1)") (class "Default")
      (node (ref "C33") (pin "1") (pinfunction "1_1") (pintype "passive"))
      (node (ref "L7") (pin "2") (pinfunction "2_2") (pintype "passive"))
      (node (ref "L8") (pin "1") (pinfunction "1_1") (pintype "passive"))
      (node (ref "R14") (pin "2") (pinfunction "2_2") (pintype "passive"))
    )
    (net (code "58") (name "Net-(C34-Pad1)") (class "Default")
      (node (ref "C34") (pin "1") (pinfunction "1_1") (pintype "passive"))
      (node (ref "L10") (pin "2") (pinfunction "2_2") (pintype "passive"))
      (node (ref "L11") (pin "1") (pinfunction "1_1") (pintype "passive"))
      (node (ref "R15") (pin "2") (pinfunction "2_2") (pintype "passive"))
    )
    (net (code "59") (name "Net-(F1-Pad2)") (class "Default")
      (node (ref "F1") (pin "2") (pinfunction "2_2") (pintype "passive"))
      (node (ref "L1") (pin "1") (pinfunction "1_1") (pintype "passive"))
    )
    (net (code "60") (name "Net-(F2-Pad2)") (class "Default")
      (node (ref "F2") (pin "2") (pinfunction "2_2") (pintype "passive"))
      (node (ref "L4") (pin "1") (pinfunction "1_1") (pintype "passive"))
    )
    (net (code "61") (name "Net-(F3-Pad2)") (class "Default")
      (node (ref "F3") (pin "2") (pinfunction "2_2") (pintype "passive"))
      (node (ref "L7") (pin "1") (pinfunction "1_1") (pintype "passive"))
    )
    (net (code "62") (name "Net-(F4-Pad2)") (class "Default")
      (node (ref "F4") (pin "2") (pinfunction "2_2") (pintype "passive"))
      (node (ref "L10") (pin "1") (pinfunction "1_1") (pintype "passive"))
    )
    (net (code "63") (name "Net-(L2-Pad2)") (class "Default")
      (node (ref "L2") (pin "2") (pinfunction "2_2") (pintype "passive"))
      (node (ref "L3") (pin "1") (pinfunction "1_1") (pintype "passive"))
      (node (ref "R12") (pin "1") (pinfunction "1_1") (pintype "passive"))
    )
    (net (code "64") (name "Net-(L5-Pad2)") (class "Default")
      (node (ref "L5") (pin "2") (pinfunction "2_2") (pintype "passive"))
      (node (ref "L6") (pin "1") (pinfunction "1_1") (pintype "passive"))
      (node (ref "R13") (pin "1") (pinfunction "1_1") (pintype "passive"))
    )
    (net (code "65") (name "Net-(L8-Pad2)") (class "Default")
      (node (ref "L8") (pin "2") (pinfunction "2_2") (pintype "passive"))
      (node (ref "L9") (pin "1") (pinfunction "1_1") (pintype "passive"))
      (node (ref "R14") (pin "1") (pinfunction "1_1") (pintype "passive"))
    )
    (net (code "66") (name "Net-(L11-Pad2)") (class "Default")
      (node (ref "L11") (pin "2") (pinfunction "2_2") (pintype "passive"))
      (node (ref "L12") (pin "1") (pinfunction "1_1") (pintype "passive"))
      (node (ref "R15") (pin "1") (pinfunction "1_1") (pintype "passive"))
    )
    (net (code "67") (name "Net-(U1A-XRES)") (class "Default")
      (node (ref "R1") (pin "2") (pinfunction "2_2") (pintype "passive"))
      (node (ref "U1") (pin "17") (pinfunction "XRES_17") (pintype "passive"))
    )
    (net (code "68") (name "unconnected-(D1-IO2-Pad2)") (class "Default")
      (node (ref "D1") (pin "2") (pinfunction "IO2_2") (pintype "bidirectional"))
    )
    (net (code "69") (name "unconnected-(D1-IO3-Pad4)") (class "Default")
      (node (ref "D1") (pin "4") (pinfunction "IO3_4") (pintype "bidirectional"))
    )
    (net (code "70") (name "unconnected-(D1-NC-Pad7)") (class "Default")
      (node (ref "D1") (pin "7") (pinfunction "NC_7") (pintype "passive"))
    )
    (net (code "71") (name "unconnected-(D1-NC-Pad9)") (class "Default")
      (node (ref "D1") (pin "9") (pinfunction "NC_9") (pintype "passive"))
    )
    (net (code "72") (name "unconnected-(D2-IO2-Pad2)") (class "Default")
      (node (ref "D2") (pin "2") (pinfunction "IO2_2") (pintype "bidirectional"))
    )
    (net (code "73") (name "unconnected-(D2-IO3-Pad4)") (class "Default")
      (node (ref "D2") (pin "4") (pinfunction "IO3_4") (pintype "bidirectional"))
    )
    (net (code "74") (name "unconnected-(D2-NC-Pad7)") (class "Default")
      (node (ref "D2") (pin "7") (pinfunction "NC_7") (pintype "passive"))
    )
    (net (code "75") (name "unconnected-(D2-NC-Pad9)") (class "Default")
      (node (ref "D2") (pin "9") (pinfunction "NC_9") (pintype "passive"))
    )
    (net (code "76") (name "unconnected-(U1A-CKCN-Pad34)") (class "Default")
      (node (ref "U1") (pin "34") (pinfunction "CKCN_34") (pintype "bidirectional+no_connect"))
    )
    (net (code "77") (name "unconnected-(U1A-CKCP-Pad33)") (class "Default")
      (node (ref "U1") (pin "33") (pinfunction "CKCP_33") (pintype "bidirectional+no_connect"))
    )
    (net (code "78") (name "unconnected-(U1A-MFP0-Pad1)") (class "Default")
      (node (ref "U1") (pin "1") (pinfunction "MFP0_1") (pintype "bidirectional+no_connect"))
    )
    (net (code "79") (name "unconnected-(U1A-MFP1-Pad2)") (class "Default")
      (node (ref "U1") (pin "2") (pinfunction "MFP1_2") (pintype "bidirectional+no_connect"))
    )
    (net (code "80") (name "unconnected-(U1A-MFP2-Pad3)") (class "Default")
      (node (ref "U1") (pin "3") (pinfunction "MFP2_3") (pintype "bidirectional+no_connect"))
    )
    (net (code "81") (name "unconnected-(U1A-MFP3-Pad12)") (class "Default")
      (node (ref "U1") (pin "12") (pinfunction "MFP3_12") (pintype "bidirectional+no_connect"))
    )
    (net (code "82") (name "unconnected-(U1A-SCL1{slash}MFP8-Pad27)") (class "Default")
      (node (ref "U1") (pin "27") (pinfunction "SCL1/MFP8_27") (pintype "bidirectional+no_connect"))
    )
    (net (code "83") (name "unconnected-(U1A-SDA1{slash}MFP7-Pad26)") (class "Default")
      (node (ref "U1") (pin "26") (pinfunction "SDA1/MFP7_26") (pintype "bidirectional+no_connect"))
    )
    (net (code "84") (name "unconnected-(U1B-NC{slash}CKFN-Pad52)") (class "Default")
      (node (ref "U1") (pin "52") (pinfunction "NC/CKFN_52") (pintype "passive+no_connect"))
    )
    (net (code "85") (name "unconnected-(U1B-NC{slash}CKFP-Pad51)") (class "Default")
      (node (ref "U1") (pin "51") (pinfunction "NC/CKFP_51") (pintype "passive+no_connect"))
    )
  )
)
